# Sheet1.net
KiCad netlist of a schematic drawn in Altium Designer
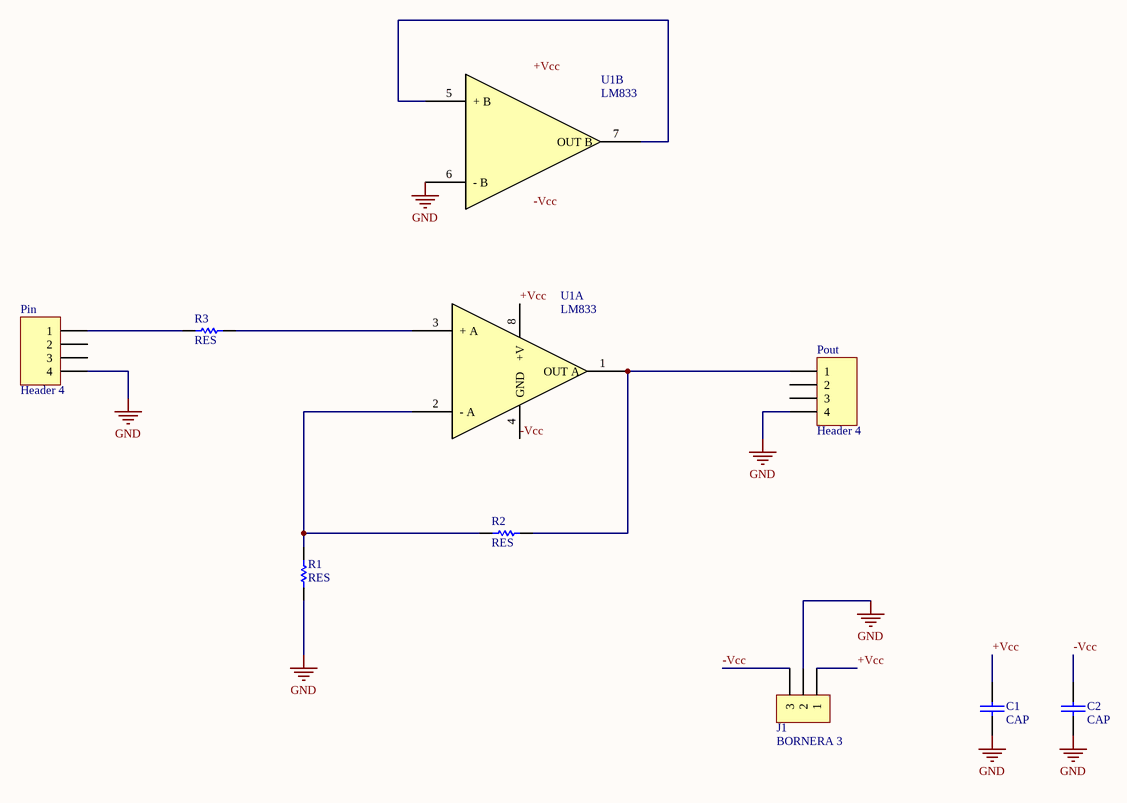
[diagram p0: Sheet1.SchDoc]

(export (version "E")
  (design (tool "Eeschema 10.0.6"))
  (components
    (comp (ref "C1") (value "CAP") (footprint "0805") (libsource (lib "LIBEBAL") (part "CAP")))
    (comp (ref "C2") (value "CAP") (footprint "0805") (libsource (lib "LIBEBAL") (part "CAP")))
    (comp (ref "J1")
      (value "BORNERA 3")
      (footprint "BORNERA3")
      (libsource (lib "LIBEBAL") (part "BORNERA 3"))
    )
    (comp (ref "Pin")
      (value "Header 4")
      (footprint "HDR1X4")
      (description "Header, 4-Pin")
      (fields (field (name "PUBLISHER") "Altium Limited"))
      (libsource (lib "Miscellaneous Connectors") (part "Header 4"))
    )
    (comp (ref "Pout")
      (value "Header 4")
      (footprint "HDR1X4")
      (description "Header, 4-Pin")
      (fields (field (name "PUBLISHER") "Altium Limited"))
      (libsource (lib "") (part "Header 4_1"))
    )
    (comp (ref "R1") (value "RES") (footprint "0805") (libsource (lib "LIBEBAL") (part "RES")))
    (comp (ref "R2") (value "RES") (footprint "0805") (libsource (lib "LIBEBAL") (part "RES")))
    (comp (ref "R3") (value "RES") (footprint "0805") (libsource (lib "LIBEBAL") (part "RES")))
    (comp (ref "U1")
      (value "LM833")
      (footprint "DIP8")
      (description "Dual Audio Operational Amplifier")
      (libsource (lib "LIBEBAL") (part "LM833"))
    )
  )
  (nets
    (net (code "1") (name "/+Vcc") (class "Default")
      (node (ref "C1") (pin "1") (pinfunction "1_1") (pintype "passive"))
      (node (ref "J1") (pin "1") (pinfunction "1_1") (pintype "passive"))
      (node (ref "U1") (pin "8") (pinfunction "+V_8") (pintype "passive"))
    )
    (net (code "2") (name "/-Vcc") (class "Default")
      (node (ref "C2") (pin "2") (pinfunction "2_2") (pintype "passive"))
      (node (ref "J1") (pin "3") (pinfunction "3_3") (pintype "passive"))
      (node (ref "U1") (pin "4") (pinfunction "GND_4") (pintype "passive"))
    )
    (net (code "3") (name "GND") (class "Default")
      (node (ref "C1") (pin "2") (pinfunction "2_2") (pintype "passive"))
      (node (ref "C2") (pin "1") (pinfunction "1_1") (pintype "passive"))
      (node (ref "J1") (pin "2") (pinfunction "2_2") (pintype "passive"))
      (node (ref "Pin") (pin "4") (pinfunction "4_4") (pintype "passive"))
      (node (ref "Pout") (pin "4") (pinfunction "4_4") (pintype "passive"))
      (node (ref "R1") (pin "1") (pinfunction "1_1") (pintype "passive"))
      (node (ref "U1") (pin "6") (pinfunction "-_B_6") (pintype "passive"))
    )
    (net (code "4") (name "Net-(Pin-Pad1)") (class "Default")
      (node (ref "Pin") (pin "1") (pinfunction "1_1") (pintype "passive"))
      (node (ref "R3") (pin "1") (pinfunction "1_1") (pintype "passive"))
    )
    (net (code "5") (name "Net-(U1A-+_A)") (class "Default")
      (node (ref "R3") (pin "2") (pinfunction "2_2") (pintype "passive"))
      (node (ref "U1") (pin "3") (pinfunction "+_A_3") (pintype "passive"))
    )
    (net (code "6") (name "Net-(U1A--_A)") (class "Default")
      (node (ref "R1") (pin "2") (pinfunction "2_2") (pintype "passive"))
      (node (ref "R2") (pin "1") (pinfunction "1_1") (pintype "passive"))
      (node (ref "U1") (pin "2") (pinfunction "-_A_2") (pintype "passive"))
    )
    (net (code "7") (name "Net-(U1A-OUT_A)") (class "Default")
      (node (ref "Pout") (pin "1") (pinfunction "1_1") (pintype "passive"))
      (node (ref "R2") (pin "2") (pinfunction "2_2") (pintype "passive"))
      (node (ref "U1") (pin "1") (pinfunction "OUT_A_1") (pintype "passive"))
    )
    (net (code "8") (name "Net-(U1B-+_B)") (class "Default")
      (node (ref "U1") (pin "5") (pinfunction "+_B_5") (pintype "passive"))
      (node (ref "U1") (pin "7") (pinfunction "OUT_B_7") (pintype "passive"))
    )
    (net (code "9") (name "unconnected-(Pin-Pad2)") (class "Default")
      (node (ref "Pin") (pin "2") (pinfunction "2_2") (pintype "passive"))
    )
    (net (code "10") (name "unconnected-(Pin-Pad3)") (class "Default")
      (node (ref "Pin") (pin "3") (pinfunction "3_3") (pintype "passive"))
    )
    (net (code "11") (name "unconnected-(Pout-Pad2)") (class "Default")
      (node (ref "Pout") (pin "2") (pinfunction "2_2") (pintype "passive"))
    )
    (net (code "12") (name "unconnected-(Pout-Pad3)") (class "Default")
      (node (ref "Pout") (pin "3") (pinfunction "3_3") (pintype "passive"))
    )
  )
)
